# Power_Circuit.net
KiCad netlist of a schematic drawn in Altium Designer
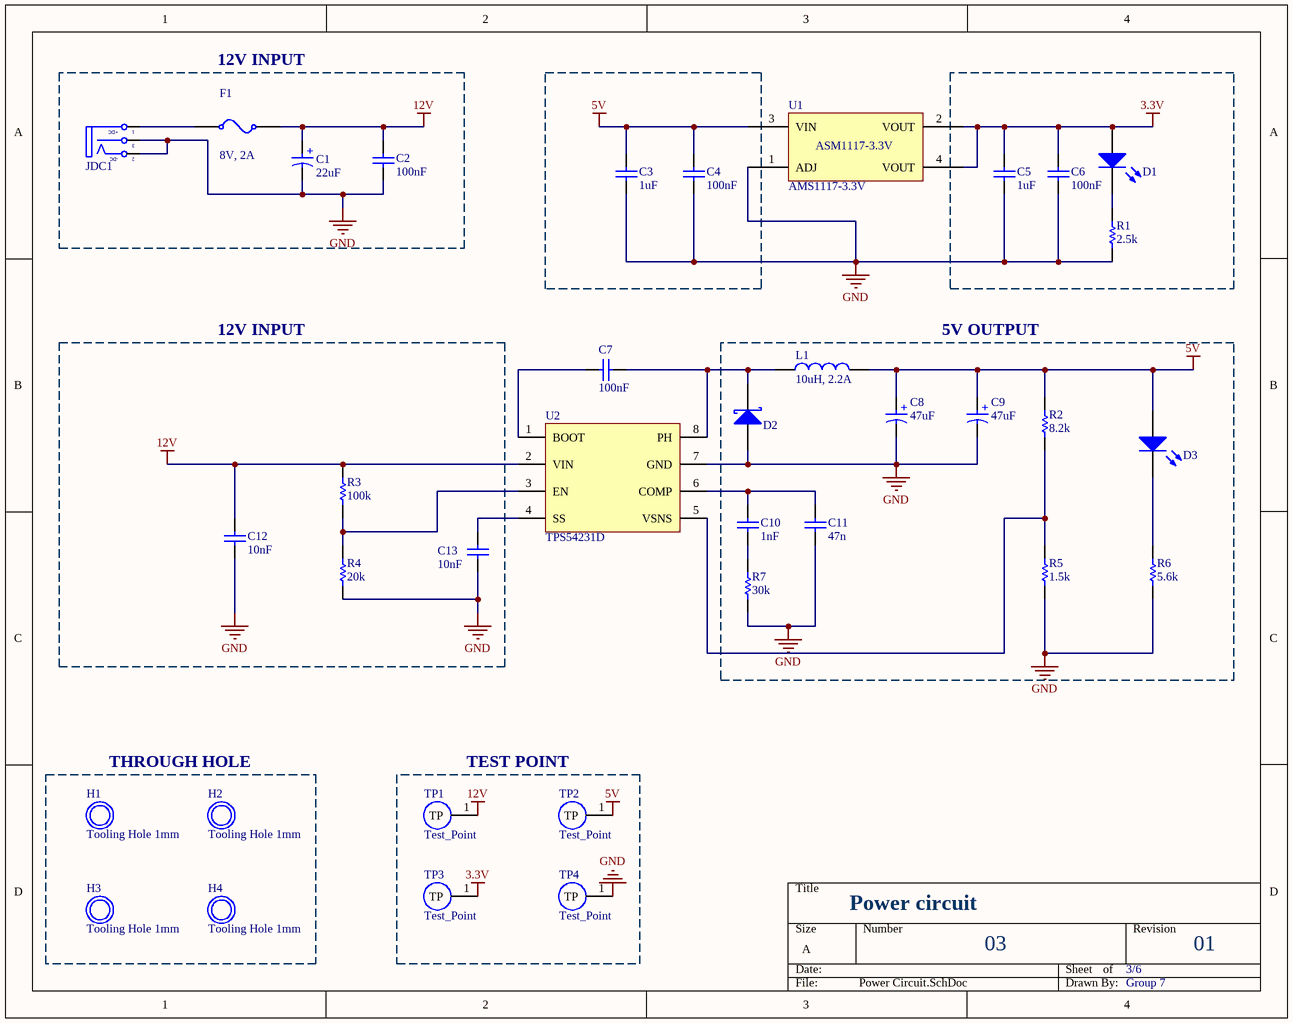
[diagram p0:  Power Circuit.SchDoc]

(export (version "E")
  (design (tool "Eeschema 10.0.6"))
  (components
    (comp (ref "C1")
      (value "22uF")
      (footprint "WCAP-ASLI_D4H5.5")
      (description "V-Chip, D4 x H5.5mm, 22uF, 16V")
      (libsource (lib "SMIOT_Lib_Schematic") (part "865080340003"))
    )
    (comp (ref "C2")
      (value "100nF")
      (footprint "CAP_0603")
      (description "CAP, size 0603, 100nF")
      (libsource (lib "SMIOT_Lib_Schematic") (part "01060310410"))
    )
    (comp (ref "C3")
      (value "1uF")
      (footprint "CAP_0603")
      (description "CAP, size 0603, 1uF")
      (libsource (lib "SMIOT_Lib_Schematic") (part "01060310510"))
    )
    (comp (ref "C4")
      (value "100nF")
      (footprint "CAP_0603")
      (description "CAP, size 0603, 100nF")
      (libsource (lib "SMIOT_Lib_Schematic") (part "01060310410"))
    )
    (comp (ref "C5")
      (value "1uF")
      (footprint "CAP_0603")
      (description "CAP, size 0603, 1uF")
      (libsource (lib "SMIOT_Lib_Schematic") (part "01060310510"))
    )
    (comp (ref "C6")
      (value "100nF")
      (footprint "CAP_0603")
      (description "CAP, size 0603, 100nF")
      (libsource (lib "SMIOT_Lib_Schematic") (part "01060310410"))
    )
    (comp (ref "C7")
      (value "100nF")
      (footprint "CAP_0603")
      (description "CAP, size 0603, 100nF")
      (libsource (lib "SMIOT_Lib_Schematic") (part "01060310410"))
    )
    (comp (ref "C8")
      (value "47uF")
      (footprint "WCAP-ASLI_D5H5.5")
      (description "V-Chip, D5 x H5.5mm, 47uF, 16V")
      (libsource (lib "SMIOT_Lib_Schematic") (part "865080342006"))
    )
    (comp (ref "C9")
      (value "47uF")
      (footprint "WCAP-ASLI_D5H5.5")
      (description "V-Chip, D5 x H5.5mm, 47uF, 16V")
      (libsource (lib "SMIOT_Lib_Schematic") (part "865080342006"))
    )
    (comp (ref "C10")
      (value "1nF")
      (footprint "CAP_0603")
      (description "CAP, size 0603, 1nF")
      (libsource (lib "SMIOT_Lib_Schematic") (part "0106031025"))
    )
    (comp (ref "C11")
      (value "47n")
      (footprint "CAP_0603")
      (description "CAP, size 0603, 47nF")
      (libsource (lib "SMIOT_Lib_Schematic") (part "01060347310"))
    )
    (comp (ref "C12")
      (value "10nF")
      (footprint "CAP_0603")
      (description "CAP, size 0603, 10nF")
      (libsource (lib "SMIOT_Lib_Schematic") (part "01060310310"))
    )
    (comp (ref "C13")
      (value "10nF")
      (footprint "CAP_0603")
      (description "CAP, size 0603, 10nF")
      (libsource (lib "SMIOT_Lib_Schematic") (part "01060310310"))
    )
    (comp (ref "D1")
      (value "LED SMD")
      (footprint "LED_0805_Blue")
      (description "LED")
      (libsource (lib "SMIOT_Lib_Schematic") (part "LED SMD"))
    )
    (comp (ref "D2")
      (value "D Schottky")
      (footprint "SS34")
      (description "Schottky Diode")
      (fields (field (name "PUBLISHER") "Altium Limited"))
      (libsource (lib "SMIOT_Lib_Schematic") (part "D Schottky"))
    )
    (comp (ref "D3")
      (value "LED SMD")
      (footprint "LED_0805_Blue")
      (description "LED")
      (libsource (lib "SMIOT_Lib_Schematic") (part "LED SMD"))
    )
    (comp (ref "F1")
      (value "8V, 2A")
      (footprint "Fuse_SMD_1812")
      (description "Resettable Fuse, Size 1812, 8V, 2A")
      (fields (field (name "MANUFACTURER") "Littelfuse"))
      (libsource (lib "SMIOT_Lib_Schematic") (part "061812200008"))
    )
    (comp (ref "H1")
      (value "Tooling Hole 1mm")
      (footprint "2mm")
      (libsource (lib "SMIOT_Lib_Schematic") (part "Tooling Hole 2mm"))
    )
    (comp (ref "H2")
      (value "Tooling Hole 1mm")
      (footprint "2mm")
      (libsource (lib "SMIOT_Lib_Schematic") (part "Tooling Hole 2mm"))
    )
    (comp (ref "H3")
      (value "Tooling Hole 1mm")
      (footprint "2mm")
      (libsource (lib "SMIOT_Lib_Schematic") (part "Tooling Hole 2mm"))
    )
    (comp (ref "H4")
      (value "Tooling Hole 1mm")
      (footprint "2mm")
      (libsource (lib "SMIOT_Lib_Schematic") (part "Tooling Hole 2mm"))
    )
    (comp (ref "JDC1")
      (value "Jack DC")
      (footprint "DC-IN")
      (description "Jack DC input")
      (libsource (lib "SMIOT_Lib_Schematic") (part "Jack DC"))
    )
    (comp (ref "L1")
      (value "10uH, 2.2A")
      (footprint "WE-PD2A_5848")
      (description "WE-PD2A SMT Power Inductor, size 5848, 10uH, 2.2A")
      (fields
        (field (name "MANUFACTURER PART NUMBER") "78477410")
        (field (name "MANUFACTURER") "Wurth Elektronik")
      )
      (libsource (lib "SMIOT_Lib_Schematic") (part "78477410"))
    )
    (comp (ref "R1")
      (value "2.5k")
      (footprint "resistor_0603")
      (description "RES, 2.5K Ohm, size 0603, 5%")
      (libsource (lib "SMIOT_Lib_Schematic") (part "0006032525"))
    )
    (comp (ref "R2")
      (value "8.2k")
      (footprint "resistor_0603")
      (description "RES, 8.2 kOhms, size 0603, 1%")
      (libsource (lib "SMIOT_Lib_Schematic") (part "0006038251"))
    )
    (comp (ref "R3")
      (value "100k")
      (footprint "resistor_0603")
      (description "RES, 100k Ohm, size 0603, 1%")
      (libsource (lib "SMIOT_Lib_Schematic") (part "0006031041"))
    )
    (comp (ref "R4")
      (value "20k")
      (footprint "resistor_0603")
      (description "RES, 20 kOhms, size 0603, 1%")
      (libsource (lib "SMIOT_Lib_Schematic") (part "0006032031"))
    )
    (comp (ref "R5")
      (value "1.5k")
      (footprint "resistor_0603")
      (description "RES, 1.5 kOhms, size 0603, 1%")
      (libsource (lib "SMIOT_Lib_Schematic") (part "0006031521"))
    )
    (comp (ref "R6")
      (value "5.6k")
      (footprint "resistor_0603")
      (description "RES, 5.6k Ohm, size 0603, 1%")
      (libsource (lib "SMIOT_Lib_Schematic") (part "0006035621"))
    )
    (comp (ref "R7")
      (value "30k")
      (footprint "resistor_0603")
      (description "RES, 30k Ohm, size 0603, 1%")
      (libsource (lib "SMIOT_Lib_Schematic") (part "0006033205"))
    )
    (comp (ref "TP1")
      (value "Test_Point")
      (footprint "TP_2MM")
      (description "Test point, 2mm radius")
      (libsource (lib "SMIOT_Lib_Schematic") (part "Test_Point"))
    )
    (comp (ref "TP2")
      (value "Test_Point")
      (footprint "TP_2MM")
      (description "Test point, 2mm radius")
      (libsource (lib "SMIOT_Lib_Schematic") (part "Test_Point"))
    )
    (comp (ref "TP3")
      (value "Test_Point")
      (footprint "TP_2MM")
      (description "Test point, 2mm radius")
      (libsource (lib "SMIOT_Lib_Schematic") (part "Test_Point"))
    )
    (comp (ref "TP4")
      (value "Test_Point")
      (footprint "TP_2MM")
      (description "Test point, 2mm radius")
      (libsource (lib "SMIOT_Lib_Schematic") (part "Test_Point"))
    )
    (comp (ref "U1")
      (value "AMS1117-3.3V")
      (footprint "AMS1117-3.3V SOT223")
      (description "AMS1117-3.3V, OUT 3.3V 1A.")
      (fields (field (name "MANUFACTURER") "AMS"))
      (libsource (lib "SMIOT_Lib_Schematic") (part "AMS1117-3.3V"))
    )
    (comp (ref "U2")
      (value "TPS54231D")
      (footprint "SOIC8")
      (description "Buck Switching Regulator IC Positive Adjustable 0.8V 1 Output 2A 8-SOIC (0.154\", 3.90mm Width)")
      (fields (field (name "MFR") "Texas Instruments"))
      (libsource (lib "SMIOT_Lib_Schematic") (part "TPS54231"))
    )
  )
  (nets
    (net (code "1") (name "3.3V") (class "Default")
      (node (ref "C5") (pin "1") (pinfunction "1_1") (pintype "passive"))
      (node (ref "C6") (pin "1") (pinfunction "1_1") (pintype "passive"))
      (node (ref "D1") (pin "1") (pinfunction "A_1") (pintype "passive"))
      (node (ref "TP3") (pin "1") (pinfunction "TP_1") (pintype "passive"))
      (node (ref "U1") (pin "2") (pinfunction "VOUT_2") (pintype "passive"))
      (node (ref "U1") (pin "4") (pinfunction "VOUT_4") (pintype "power_in"))
    )
    (net (code "2") (name "5V") (class "Default")
      (node (ref "C3") (pin "1") (pinfunction "1_1") (pintype "passive"))
      (node (ref "C4") (pin "1") (pinfunction "1_1") (pintype "passive"))
      (node (ref "C8") (pin "1") (pinfunction "P_1") (pintype "passive"))
      (node (ref "C9") (pin "1") (pinfunction "P_1") (pintype "passive"))
      (node (ref "D3") (pin "1") (pinfunction "A_1") (pintype "passive"))
      (node (ref "L1") (pin "2") (pinfunction "2_2") (pintype "passive"))
      (node (ref "R2") (pin "2") (pinfunction "2_2") (pintype "passive"))
      (node (ref "TP2") (pin "1") (pinfunction "TP_1") (pintype "passive"))
      (node (ref "U1") (pin "3") (pinfunction "VIN_3") (pintype "passive"))
    )
    (net (code "3") (name "12V") (class "Default")
      (node (ref "C1") (pin "1") (pinfunction "P_1") (pintype "passive"))
      (node (ref "C12") (pin "1") (pinfunction "1_1") (pintype "passive"))
      (node (ref "C2") (pin "1") (pinfunction "1_1") (pintype "passive"))
      (node (ref "F1") (pin "1") (pinfunction "1_1") (pintype "passive"))
      (node (ref "R3") (pin "1") (pinfunction "1_1") (pintype "passive"))
      (node (ref "TP1") (pin "1") (pinfunction "TP_1") (pintype "passive"))
      (node (ref "U2") (pin "2") (pinfunction "VIN_2") (pintype "passive"))
    )
    (net (code "4") (name "GND") (class "Default")
      (node (ref "C1") (pin "2") (pinfunction "N_2") (pintype "passive"))
      (node (ref "C11") (pin "2") (pinfunction "2_2") (pintype "passive"))
      (node (ref "C12") (pin "2") (pinfunction "2_2") (pintype "passive"))
      (node (ref "C13") (pin "2") (pinfunction "2_2") (pintype "passive"))
      (node (ref "C2") (pin "2") (pinfunction "2_2") (pintype "passive"))
      (node (ref "C3") (pin "2") (pinfunction "2_2") (pintype "passive"))
      (node (ref "C4") (pin "2") (pinfunction "2_2") (pintype "passive"))
      (node (ref "C5") (pin "2") (pinfunction "2_2") (pintype "passive"))
      (node (ref "C6") (pin "2") (pinfunction "2_2") (pintype "passive"))
      (node (ref "C8") (pin "2") (pinfunction "N_2") (pintype "passive"))
      (node (ref "C9") (pin "2") (pinfunction "N_2") (pintype "passive"))
      (node (ref "D2") (pin "1") (pinfunction "A_1") (pintype "passive"))
      (node (ref "JDC1") (pin "2") (pinfunction "TN_2") (pintype "passive"))
      (node (ref "JDC1") (pin "3") (pinfunction "S_3") (pintype "power_in"))
      (node (ref "R1") (pin "2") (pinfunction "2_2") (pintype "passive"))
      (node (ref "R4") (pin "2") (pinfunction "2_2") (pintype "passive"))
      (node (ref "R5") (pin "2") (pinfunction "2_2") (pintype "passive"))
      (node (ref "R6") (pin "2") (pinfunction "2_2") (pintype "passive"))
      (node (ref "R7") (pin "2") (pinfunction "2_2") (pintype "passive"))
      (node (ref "TP4") (pin "1") (pinfunction "TP_1") (pintype "passive"))
      (node (ref "U1") (pin "1") (pinfunction "ADJ_1") (pintype "power_in"))
      (node (ref "U2") (pin "7") (pinfunction "GND_7") (pintype "passive"))
    )
    (net (code "5") (name "Net-(C10-Pad2)") (class "Default")
      (node (ref "C10") (pin "2") (pinfunction "2_2") (pintype "passive"))
      (node (ref "R7") (pin "1") (pinfunction "1_1") (pintype "passive"))
    )
    (net (code "6") (name "Net-(D1-K)") (class "Default")
      (node (ref "D1") (pin "2") (pinfunction "K_2") (pintype "passive"))
      (node (ref "R1") (pin "1") (pinfunction "1_1") (pintype "passive"))
    )
    (net (code "7") (name "Net-(D2-K)") (class "Default")
      (node (ref "C7") (pin "2") (pinfunction "2_2") (pintype "passive"))
      (node (ref "D2") (pin "2") (pinfunction "K_2") (pintype "passive"))
      (node (ref "L1") (pin "1") (pinfunction "1_1") (pintype "passive"))
      (node (ref "U2") (pin "8") (pinfunction "PH_8") (pintype "passive"))
    )
    (net (code "8") (name "Net-(D3-K)") (class "Default")
      (node (ref "D3") (pin "2") (pinfunction "K_2") (pintype "passive"))
      (node (ref "R6") (pin "1") (pinfunction "1_1") (pintype "passive"))
    )
    (net (code "9") (name "Net-(JDC1-T)") (class "Default")
      (node (ref "F1") (pin "0") (pinfunction "0_0") (pintype "passive"))
      (node (ref "JDC1") (pin "1") (pinfunction "T_1") (pintype "passive"))
    )
    (net (code "10") (name "Net-(U2-BOOT)") (class "Default")
      (node (ref "C7") (pin "1") (pinfunction "1_1") (pintype "passive"))
      (node (ref "U2") (pin "1") (pinfunction "BOOT_1") (pintype "passive"))
    )
    (net (code "11") (name "Net-(U2-COMP)") (class "Default")
      (node (ref "C10") (pin "1") (pinfunction "1_1") (pintype "passive"))
      (node (ref "C11") (pin "1") (pinfunction "1_1") (pintype "passive"))
      (node (ref "U2") (pin "6") (pinfunction "COMP_6") (pintype "passive"))
    )
    (net (code "12") (name "Net-(U2-EN)") (class "Default")
      (node (ref "R3") (pin "2") (pinfunction "2_2") (pintype "passive"))
      (node (ref "R4") (pin "1") (pinfunction "1_1") (pintype "passive"))
      (node (ref "U2") (pin "3") (pinfunction "EN_3") (pintype "passive"))
    )
    (net (code "13") (name "Net-(U2-SS)") (class "Default")
      (node (ref "C13") (pin "1") (pinfunction "1_1") (pintype "passive"))
      (node (ref "U2") (pin "4") (pinfunction "SS_4") (pintype "passive"))
    )
    (net (code "14") (name "Net-(U2-VSNS)") (class "Default")
      (node (ref "R2") (pin "1") (pinfunction "1_1") (pintype "passive"))
      (node (ref "R5") (pin "1") (pinfunction "1_1") (pintype "passive"))
      (node (ref "U2") (pin "5") (pinfunction "VSNS_5") (pintype "passive"))
    )
  )
)
